# Mako_DSP_SD_Card_and_MIDI_R2_1.net
KiCad netlist of a schematic drawn in Altium Designer
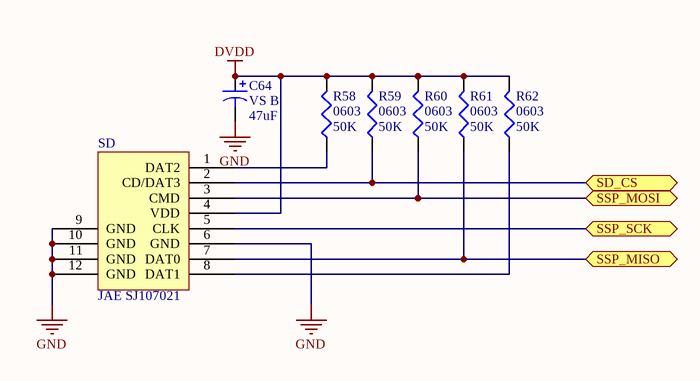
[diagram p0: Mako DSP SD Card and MIDI R2.1.SchDoc]

(export (version "E")
  (design (tool "Eeschema 10.0.6"))
  (components
    (comp (ref "C64")
      (value "VS B")
      (footprint "Panasonic VS B")
      (description "Polarized Capacitor (Radial)")
      (fields (field (name "ALTIUM_VALUE") "47uF") (field (name "PUBLISHER") "Altium Limited"))
      (libsource (lib "Miscellaneous Devices") (part "Cap Pol1"))
    )
    (comp (ref "R58")
      (value "0603")
      (footprint "J1-0603")
      (description "Resistor")
      (fields (field (name "ALTIUM_VALUE") "50K") (field (name "PUBLISHER") "Altium Limited"))
      (libsource (lib "Miscellaneous Devices") (part "Res3"))
    )
    (comp (ref "R59")
      (value "0603")
      (footprint "J1-0603")
      (description "Resistor")
      (fields (field (name "ALTIUM_VALUE") "50K") (field (name "PUBLISHER") "Altium Limited"))
      (libsource (lib "Miscellaneous Devices") (part "Res3"))
    )
    (comp (ref "R60")
      (value "0603")
      (footprint "J1-0603")
      (description "Resistor")
      (fields (field (name "ALTIUM_VALUE") "50K") (field (name "PUBLISHER") "Altium Limited"))
      (libsource (lib "Miscellaneous Devices") (part "Res3"))
    )
    (comp (ref "R61")
      (value "0603")
      (footprint "J1-0603")
      (description "Resistor")
      (fields (field (name "ALTIUM_VALUE") "50K") (field (name "PUBLISHER") "Altium Limited"))
      (libsource (lib "Miscellaneous Devices") (part "Res3"))
    )
    (comp (ref "R62")
      (value "0603")
      (footprint "J1-0603")
      (description "Resistor")
      (fields (field (name "ALTIUM_VALUE") "50K") (field (name "PUBLISHER") "Altium Limited"))
      (libsource (lib "Miscellaneous Devices") (part "Res3"))
    )
    (comp (ref "SD")
      (value "JAE SJ107021")
      (footprint "JAE SJ107021")
      (libsource (lib "Adams Altium Library") (part "JAE SJ107021 microSD Card Socket"))
    )
  )
  (nets
    (net (code "1") (name "/SD_CS") (class "Default")
      (node (ref "R59") (pin "1") (pinfunction "1_1") (pintype "passive"))
      (node (ref "SD") (pin "2") (pinfunction "CD/DAT3_2") (pintype "passive"))
    )
    (net (code "2") (name "/SSP_MISO") (class "Default")
      (node (ref "R61") (pin "1") (pinfunction "1_1") (pintype "passive"))
      (node (ref "SD") (pin "7") (pinfunction "DAT0_7") (pintype "passive"))
    )
    (net (code "3") (name "/SSP_MOSI") (class "Default")
      (node (ref "R60") (pin "1") (pinfunction "1_1") (pintype "passive"))
      (node (ref "SD") (pin "3") (pinfunction "CMD_3") (pintype "passive"))
    )
    (net (code "4") (name "/SSP_SCK") (class "Default")
      (node (ref "SD") (pin "5") (pinfunction "CLK_5") (pintype "passive"))
    )
    (net (code "5") (name "DVDD") (class "Default")
      (node (ref "C64") (pin "1") (pinfunction "1_1") (pintype "passive"))
      (node (ref "R58") (pin "2") (pinfunction "2_2") (pintype "passive"))
      (node (ref "R59") (pin "2") (pinfunction "2_2") (pintype "passive"))
      (node (ref "R60") (pin "2") (pinfunction "2_2") (pintype "passive"))
      (node (ref "R61") (pin "2") (pinfunction "2_2") (pintype "passive"))
      (node (ref "R62") (pin "2") (pinfunction "2_2") (pintype "passive"))
      (node (ref "SD") (pin "4") (pinfunction "VDD_4") (pintype "passive"))
    )
    (net (code "6") (name "GND") (class "Default")
      (node (ref "C64") (pin "2") (pinfunction "2_2") (pintype "passive"))
      (node (ref "SD") (pin "10") (pinfunction "GND_10") (pintype "passive"))
      (node (ref "SD") (pin "11") (pinfunction "GND_11") (pintype "passive"))
      (node (ref "SD") (pin "12") (pinfunction "GND_12") (pintype "passive"))
      (node (ref "SD") (pin "6") (pinfunction "GND_6") (pintype "passive"))
      (node (ref "SD") (pin "9") (pinfunction "GND_9") (pintype "passive"))
    )
    (net (code "7") (name "Net-(SD-DAT1)") (class "Default")
      (node (ref "R62") (pin "1") (pinfunction "1_1") (pintype "passive"))
      (node (ref "SD") (pin "8") (pinfunction "DAT1_8") (pintype "passive"))
    )
    (net (code "8") (name "Net-(SD-DAT2)") (class "Default")
      (node (ref "R58") (pin "1") (pinfunction "1_1") (pintype "passive"))
      (node (ref "SD") (pin "1") (pinfunction "DAT2_1") (pintype "passive"))
    )
  )
)
